# minutka_hlavni_v2.net
KiCad netlist of a schematic drawn in EAGLE
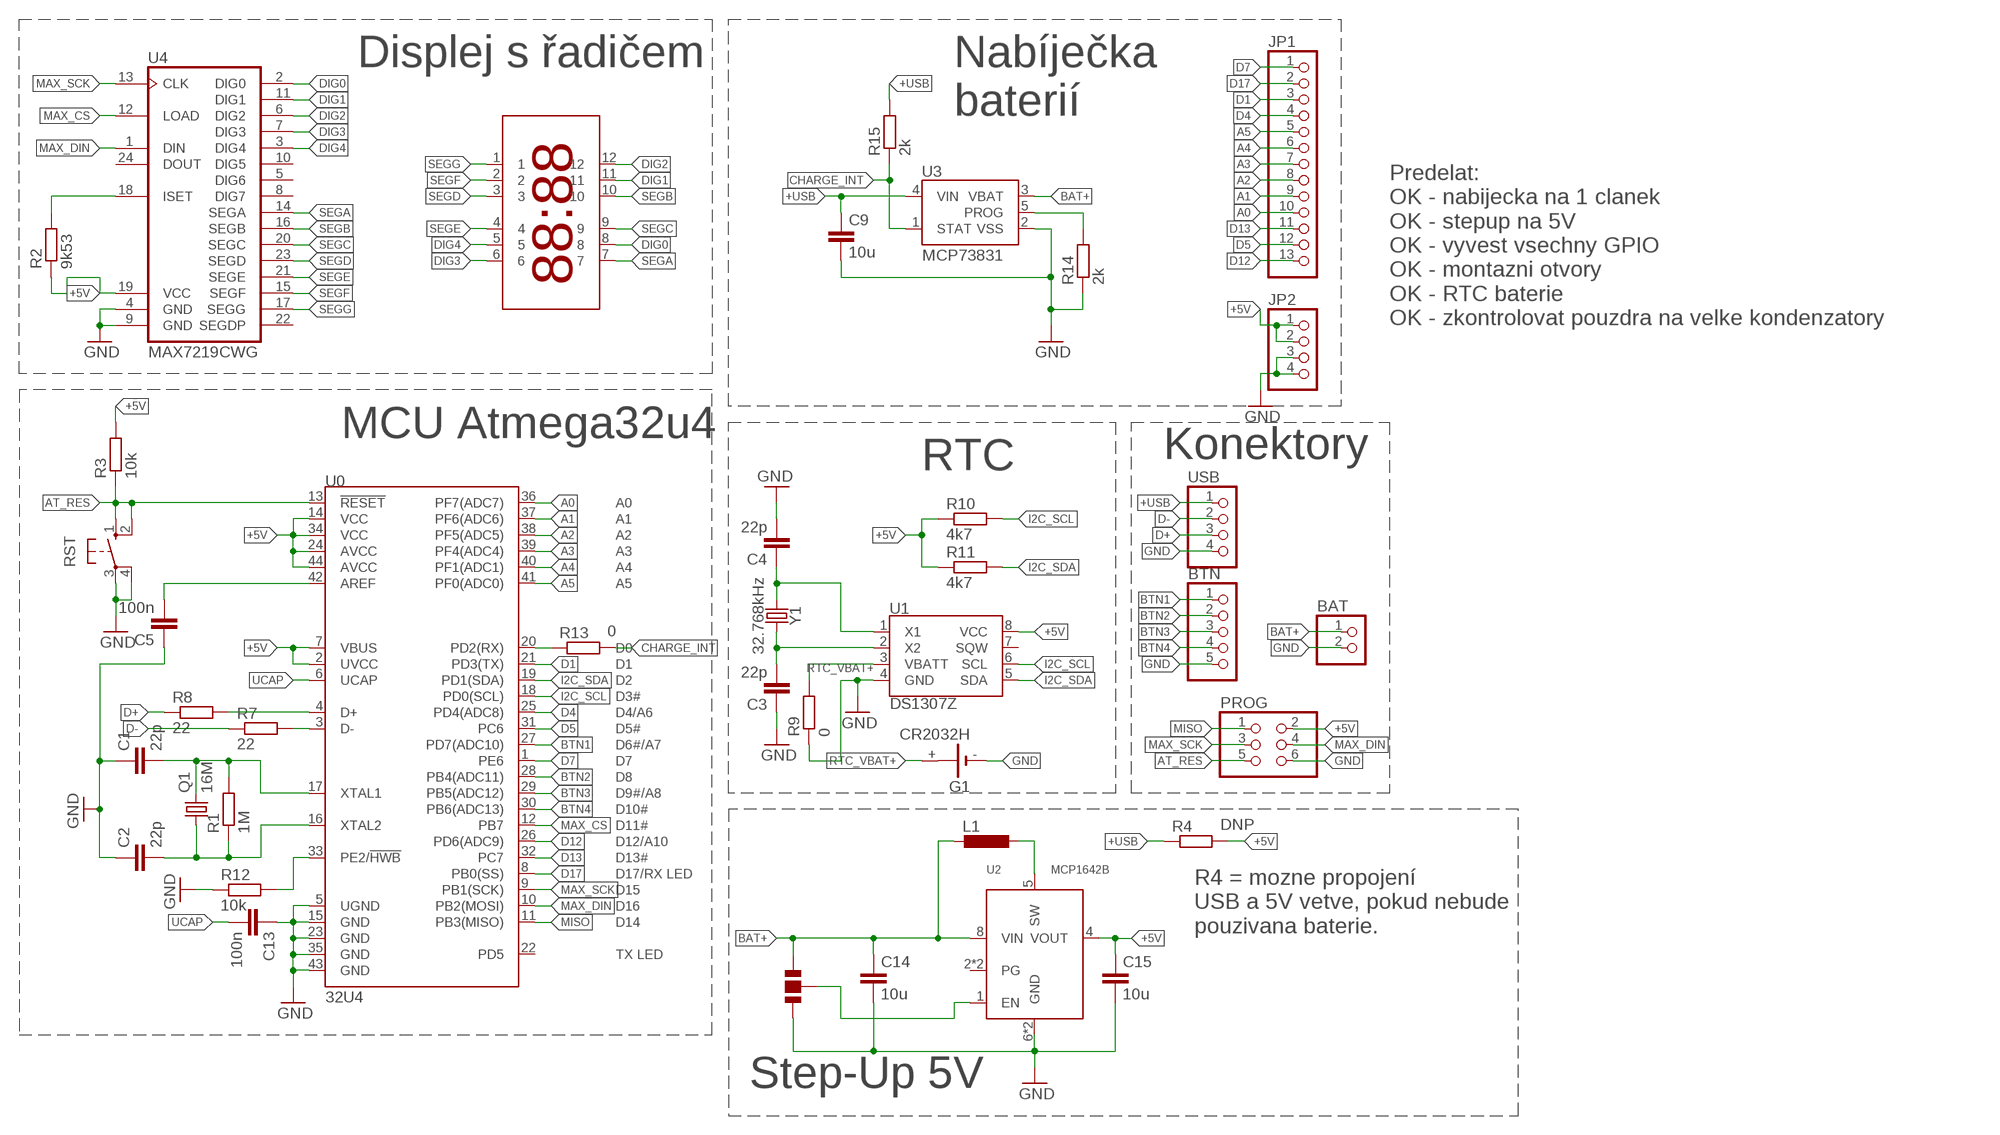
[diagram p0: schematic, sheet 1]

(export (version "E")
  (design (tool "Eeschema 10.0.6"))
  (components
    (comp (ref "BAT")
      (value "PINHD-1X2")
      (footprint "eagle-import:1X02")
      (libsource (lib "eagle-import") (part "PINHD-1X2"))
    )
    (comp (ref "BTN")
      (value "PINHD-1X5")
      (footprint "eagle-import:1X05")
      (libsource (lib "eagle-import") (part "PINHD-1X5"))
    )
    (comp (ref "C1")
      (value "22p")
      (footprint "eagle-import:C0603")
      (libsource (lib "eagle-import") (part "C-EUC0603"))
    )
    (comp (ref "C2")
      (value "22p")
      (footprint "eagle-import:C0603")
      (libsource (lib "eagle-import") (part "C-EUC0603"))
    )
    (comp (ref "C3")
      (value "22p")
      (footprint "eagle-import:C0603")
      (libsource (lib "eagle-import") (part "C-EUC0603"))
    )
    (comp (ref "C4")
      (value "22p")
      (footprint "eagle-import:C0603")
      (libsource (lib "eagle-import") (part "C-EUC0603"))
    )
    (comp (ref "C5")
      (value "100n")
      (footprint "eagle-import:C0603")
      (libsource (lib "eagle-import") (part "C-EUC0603"))
    )
    (comp (ref "C9")
      (value "10u")
      (footprint "eagle-import:C1206")
      (libsource (lib "eagle-import") (part "C-EUC1206"))
    )
    (comp (ref "C13")
      (value "100n")
      (footprint "eagle-import:C0603")
      (libsource (lib "eagle-import") (part "C-EUC0603"))
    )
    (comp (ref "C14")
      (value "10u")
      (footprint "eagle-import:C1206")
      (libsource (lib "eagle-import") (part "C-EUC1206"))
    )
    (comp (ref "C15")
      (value "10u")
      (footprint "eagle-import:C1206")
      (libsource (lib "eagle-import") (part "C-EUC1206"))
    )
    (comp (ref "G1")
      (value "CR2032H")
      (footprint "eagle-import:CR2032H")
      (libsource (lib "eagle-import") (part "CR2032H"))
    )
    (comp (ref "JP1")
      (value "PINHD-1X13")
      (footprint "eagle-import:1X13")
      (libsource (lib "eagle-import") (part "PINHD-1X13"))
    )
    (comp (ref "JP2")
      (value "PINHD-1X4")
      (footprint "eagle-import:1X04")
      (libsource (lib "eagle-import") (part "PINHD-1X4"))
    )
    (comp (ref "L1")
      (value "L-EUL4532P")
      (footprint "eagle-import:L4532P")
      (libsource (lib "eagle-import") (part "L-EUL4532P"))
    )
    (comp (ref "PROG")
      (value "PINHD-2X3")
      (footprint "eagle-import:2X03")
      (libsource (lib "eagle-import") (part "PINHD-2X3"))
    )
    (comp (ref "Q1")
      (value "16M")
      (footprint "eagle-import:HC49UP")
      (libsource (lib "eagle-import") (part "CRYSTALHC49UP"))
    )
    (comp (ref "R1")
      (value "1M")
      (footprint "eagle-import:R0603")
      (libsource (lib "eagle-import") (part "R-EU_R0603"))
    )
    (comp (ref "R2")
      (value "9k53")
      (footprint "eagle-import:R0603")
      (libsource (lib "eagle-import") (part "R-EU_R0603"))
    )
    (comp (ref "R3")
      (value "10k")
      (footprint "eagle-import:R0603")
      (libsource (lib "eagle-import") (part "R-EU_R0603"))
    )
    (comp (ref "R4")
      (value "DNP")
      (footprint "eagle-import:R0603")
      (libsource (lib "eagle-import") (part "R-EU_R0603"))
    )
    (comp (ref "R7")
      (value "22")
      (footprint "eagle-import:R0603")
      (libsource (lib "eagle-import") (part "R-EU_R0603"))
    )
    (comp (ref "R8")
      (value "22")
      (footprint "eagle-import:R0603")
      (libsource (lib "eagle-import") (part "R-EU_R0603"))
    )
    (comp (ref "R9")
      (value "0")
      (footprint "eagle-import:R0603")
      (libsource (lib "eagle-import") (part "R-EU_R0603"))
    )
    (comp (ref "R10")
      (value "4k7")
      (footprint "eagle-import:R0603")
      (libsource (lib "eagle-import") (part "R-EU_R0603"))
    )
    (comp (ref "R11")
      (value "4k7")
      (footprint "eagle-import:R0603")
      (libsource (lib "eagle-import") (part "R-EU_R0603"))
    )
    (comp (ref "R12")
      (value "10k")
      (footprint "eagle-import:R0603")
      (libsource (lib "eagle-import") (part "R-EU_R0603"))
    )
    (comp (ref "R13")
      (value "0")
      (footprint "eagle-import:R0603")
      (libsource (lib "eagle-import") (part "R-EU_R0603"))
    )
    (comp (ref "R14")
      (value "2k")
      (footprint "eagle-import:R0603")
      (libsource (lib "eagle-import") (part "R-EU_R0603"))
    )
    (comp (ref "R15")
      (value "2k")
      (footprint "eagle-import:R0603")
      (libsource (lib "eagle-import") (part "R-EU_R0603"))
    )
    (comp (ref "RST")
      (value "10-XX")
      (footprint "eagle-import:B3F-10XX")
      (fields (field (name "MPN") "B3F-1000"))
      (libsource (lib "eagle-import") (part "10-XX"))
    )
    (comp (ref "U$2")
      (value "KW4-8828AVB")
      (footprint "eagle-import:KW4-8828AVB")
      (libsource (lib "eagle-import") (part "KW4-8828AVB"))
    )
    (comp (ref "U$7")
      (value "JUMPER")
      (footprint "eagle-import:2-WAY")
      (libsource (lib "eagle-import") (part "JUMPER"))
    )
    (comp (ref "U0")
      (value "32U4")
      (footprint "eagle-import:TQFP44")
      (libsource (lib "eagle-import") (part "ATMEGA32U4TQFP-44"))
    )
    (comp (ref "U1")
      (value "DS1307Z")
      (footprint "eagle-import:SO08-0.15")
      (libsource (lib "eagle-import") (part "DS1307Z"))
    )
    (comp (ref "U2")
      (value "MCP1642B")
      (footprint "eagle-import:MSOP8")
      (libsource (lib "eagle-import") (part "MCP1642B"))
    )
    (comp (ref "U3")
      (value "MCP73831")
      (footprint "eagle-import:SOT95P290X120-5")
      (libsource (lib "eagle-import") (part "MCP73831"))
    )
    (comp (ref "U4")
      (value "MAX7219CWG")
      (footprint "eagle-import:SO24L")
      (libsource (lib "eagle-import") (part "MAX7219CWG"))
    )
    (comp (ref "USB")
      (value "PINHD-1X4")
      (footprint "eagle-import:1X04")
      (libsource (lib "eagle-import") (part "PINHD-1X4"))
    )
    (comp (ref "Y1")
      (value "32.768kHz")
      (footprint "eagle-import:CRYSTAL-SMD-2X6-CYL")
      (libsource (lib "eagle-import") (part "CRYSTAL-32.768KHZSMD-2X6"))
    )
  )
  (nets
    (net (code "1") (name "+5V") (class "Default")
      (node (ref "C15") (pin "1") (pinfunction "1_1") (pintype "passive"))
      (node (ref "JP2") (pin "1") (pinfunction "1_1") (pintype "passive"))
      (node (ref "JP2") (pin "2") (pinfunction "2_2") (pintype "passive"))
      (node (ref "PROG") (pin "2") (pinfunction "2_2") (pintype "passive"))
      (node (ref "R10") (pin "1") (pinfunction "1_1") (pintype "passive"))
      (node (ref "R11") (pin "1") (pinfunction "1_1") (pintype "passive"))
      (node (ref "R2") (pin "1") (pinfunction "1_1") (pintype "passive"))
      (node (ref "R3") (pin "2") (pinfunction "2_2") (pintype "passive"))
      (node (ref "R4") (pin "2") (pinfunction "2_2") (pintype "passive"))
      (node (ref "U0") (pin "14") (pinfunction "VCC_14") (pintype "bidirectional"))
      (node (ref "U0") (pin "2") (pinfunction "UVCC_2") (pintype "bidirectional"))
      (node (ref "U0") (pin "24") (pinfunction "AVCC_24") (pintype "bidirectional"))
      (node (ref "U0") (pin "34") (pinfunction "VCC_34") (pintype "bidirectional"))
      (node (ref "U0") (pin "44") (pinfunction "AVCC_44") (pintype "bidirectional"))
      (node (ref "U0") (pin "7") (pinfunction "VBUS_7") (pintype "bidirectional"))
      (node (ref "U1") (pin "8") (pinfunction "VCC_8") (pintype "bidirectional"))
      (node (ref "U2") (pin "4") (pinfunction "VOUT_4") (pintype "power_in"))
      (node (ref "U4") (pin "19") (pinfunction "VCC_19") (pintype "power_in"))
    )
    (net (code "2") (name "+USB") (class "Default")
      (node (ref "C9") (pin "1") (pinfunction "1_1") (pintype "passive"))
      (node (ref "R15") (pin "2") (pinfunction "2_2") (pintype "passive"))
      (node (ref "R4") (pin "1") (pinfunction "1_1") (pintype "passive"))
      (node (ref "U3") (pin "4") (pinfunction "VIN_4") (pintype "power_in"))
      (node (ref "USB") (pin "1") (pinfunction "1_1") (pintype "passive"))
    )
    (net (code "3") (name "A0") (class "Default")
      (node (ref "JP1") (pin "10") (pinfunction "10_10") (pintype "passive"))
      (node (ref "U0") (pin "36") (pinfunction "PF7(ADC7)_36") (pintype "bidirectional"))
    )
    (net (code "4") (name "A1") (class "Default")
      (node (ref "JP1") (pin "9") (pinfunction "9_9") (pintype "passive"))
      (node (ref "U0") (pin "37") (pinfunction "PF6(ADC6)_37") (pintype "bidirectional"))
    )
    (net (code "5") (name "A2") (class "Default")
      (node (ref "JP1") (pin "8") (pinfunction "8_8") (pintype "passive"))
      (node (ref "U0") (pin "38") (pinfunction "PF5(ADC5)_38") (pintype "bidirectional"))
    )
    (net (code "6") (name "A3") (class "Default")
      (node (ref "JP1") (pin "7") (pinfunction "7_7") (pintype "passive"))
      (node (ref "U0") (pin "39") (pinfunction "PF4(ADC4)_39") (pintype "bidirectional"))
    )
    (net (code "7") (name "A4") (class "Default")
      (node (ref "JP1") (pin "6") (pinfunction "6_6") (pintype "passive"))
      (node (ref "U0") (pin "40") (pinfunction "PF1(ADC1)_40") (pintype "bidirectional"))
    )
    (net (code "8") (name "A5") (class "Default")
      (node (ref "JP1") (pin "5") (pinfunction "5_5") (pintype "passive"))
      (node (ref "U0") (pin "41") (pinfunction "PF0(ADC0)_41") (pintype "bidirectional"))
    )
    (net (code "9") (name "AT_RES") (class "Default")
      (node (ref "PROG") (pin "5") (pinfunction "5_5") (pintype "passive"))
      (node (ref "R3") (pin "1") (pinfunction "1_1") (pintype "passive"))
      (node (ref "RST") (pin "1") (pinfunction "S_1") (pintype "passive"))
      (node (ref "RST") (pin "2") (pinfunction "S1_2") (pintype "passive"))
      (node (ref "U0") (pin "13") (pinfunction "~{RESET}_13") (pintype "bidirectional"))
    )
    (net (code "10") (name "BAT+") (class "Default")
      (node (ref "BAT") (pin "1") (pinfunction "1_1") (pintype "passive"))
      (node (ref "C14") (pin "1") (pinfunction "1_1") (pintype "passive"))
      (node (ref "L1") (pin "2") (pinfunction "2_2") (pintype "passive"))
      (node (ref "U$7") (pin "P$2") (pinfunction "P$2_P$2") (pintype "bidirectional"))
      (node (ref "U2") (pin "8") (pinfunction "VIN_8") (pintype "power_in"))
      (node (ref "U3") (pin "3") (pinfunction "VBAT_3") (pintype "power_in"))
    )
    (net (code "11") (name "BTN1") (class "Default")
      (node (ref "BTN") (pin "1") (pinfunction "1_1") (pintype "passive"))
      (node (ref "U0") (pin "27") (pinfunction "PD7(ADC10)_27") (pintype "bidirectional"))
    )
    (net (code "12") (name "BTN2") (class "Default")
      (node (ref "BTN") (pin "2") (pinfunction "2_2") (pintype "passive"))
      (node (ref "U0") (pin "28") (pinfunction "PB4(ADC11)_28") (pintype "bidirectional"))
    )
    (net (code "13") (name "BTN3") (class "Default")
      (node (ref "BTN") (pin "3") (pinfunction "3_3") (pintype "passive"))
      (node (ref "U0") (pin "29") (pinfunction "PB5(ADC12)_29") (pintype "bidirectional"))
    )
    (net (code "14") (name "BTN4") (class "Default")
      (node (ref "BTN") (pin "4") (pinfunction "4_4") (pintype "passive"))
      (node (ref "U0") (pin "30") (pinfunction "PB6(ADC13)_30") (pintype "bidirectional"))
    )
    (net (code "15") (name "CHARGE_INT") (class "Default")
      (node (ref "R13") (pin "2") (pinfunction "2_2") (pintype "passive"))
      (node (ref "R15") (pin "1") (pinfunction "1_1") (pintype "passive"))
      (node (ref "U3") (pin "1") (pinfunction "STAT_1") (pintype "output"))
    )
    (net (code "16") (name "D+") (class "Default")
      (node (ref "R8") (pin "1") (pinfunction "1_1") (pintype "passive"))
      (node (ref "USB") (pin "3") (pinfunction "3_3") (pintype "passive"))
    )
    (net (code "17") (name "D-") (class "Default")
      (node (ref "R7") (pin "1") (pinfunction "1_1") (pintype "passive"))
      (node (ref "USB") (pin "2") (pinfunction "2_2") (pintype "passive"))
    )
    (net (code "18") (name "D1") (class "Default")
      (node (ref "JP1") (pin "3") (pinfunction "3_3") (pintype "passive"))
      (node (ref "U0") (pin "21") (pinfunction "PD3(TX)_21") (pintype "bidirectional"))
    )
    (net (code "19") (name "D4") (class "Default")
      (node (ref "JP1") (pin "4") (pinfunction "4_4") (pintype "passive"))
      (node (ref "U0") (pin "25") (pinfunction "PD4(ADC8)_25") (pintype "bidirectional"))
    )
    (net (code "20") (name "D5") (class "Default")
      (node (ref "JP1") (pin "12") (pinfunction "12_12") (pintype "passive"))
      (node (ref "U0") (pin "31") (pinfunction "PC6_31") (pintype "bidirectional"))
    )
    (net (code "21") (name "D7") (class "Default")
      (node (ref "JP1") (pin "1") (pinfunction "1_1") (pintype "passive"))
      (node (ref "U0") (pin "1") (pinfunction "PE6_1") (pintype "bidirectional"))
    )
    (net (code "22") (name "D12") (class "Default")
      (node (ref "JP1") (pin "13") (pinfunction "13_13") (pintype "passive"))
      (node (ref "U0") (pin "26") (pinfunction "PD6(ADC9)_26") (pintype "bidirectional"))
    )
    (net (code "23") (name "D13") (class "Default")
      (node (ref "JP1") (pin "11") (pinfunction "11_11") (pintype "passive"))
      (node (ref "U0") (pin "32") (pinfunction "PC7_32") (pintype "bidirectional"))
    )
    (net (code "24") (name "D17") (class "Default")
      (node (ref "JP1") (pin "2") (pinfunction "2_2") (pintype "passive"))
      (node (ref "U0") (pin "8") (pinfunction "PB0(SS)_8") (pintype "bidirectional"))
    )
    (net (code "25") (name "DIG0") (class "Default")
      (node (ref "U$2") (pin "8") (pinfunction "8_8") (pintype "bidirectional"))
      (node (ref "U4") (pin "2") (pinfunction "DIG0_2") (pintype "output"))
    )
    (net (code "26") (name "DIG1") (class "Default")
      (node (ref "U$2") (pin "11") (pinfunction "11_11") (pintype "bidirectional"))
      (node (ref "U4") (pin "11") (pinfunction "DIG1_11") (pintype "output"))
    )
    (net (code "27") (name "DIG2") (class "Default")
      (node (ref "U$2") (pin "12") (pinfunction "12_12") (pintype "bidirectional"))
      (node (ref "U4") (pin "6") (pinfunction "DIG2_6") (pintype "output"))
    )
    (net (code "28") (name "DIG3") (class "Default")
      (node (ref "U$2") (pin "6") (pinfunction "6_6") (pintype "bidirectional"))
      (node (ref "U4") (pin "7") (pinfunction "DIG3_7") (pintype "output"))
    )
    (net (code "29") (name "DIG4") (class "Default")
      (node (ref "U$2") (pin "5") (pinfunction "5_5") (pintype "bidirectional"))
      (node (ref "U4") (pin "3") (pinfunction "DIG4_3") (pintype "output"))
    )
    (net (code "30") (name "GND") (class "Default")
      (node (ref "BAT") (pin "2") (pinfunction "2_2") (pintype "passive"))
      (node (ref "BTN") (pin "5") (pinfunction "5_5") (pintype "passive"))
      (node (ref "C1") (pin "1") (pinfunction "1_1") (pintype "passive"))
      (node (ref "C13") (pin "1") (pinfunction "1_1") (pintype "passive"))
      (node (ref "C14") (pin "2") (pinfunction "2_2") (pintype "passive"))
      (node (ref "C15") (pin "2") (pinfunction "2_2") (pintype "passive"))
      (node (ref "C2") (pin "1") (pinfunction "1_1") (pintype "passive"))
      (node (ref "C3") (pin "1") (pinfunction "1_1") (pintype "passive"))
      (node (ref "C4") (pin "2") (pinfunction "2_2") (pintype "passive"))
      (node (ref "C5") (pin "1") (pinfunction "1_1") (pintype "passive"))
      (node (ref "C9") (pin "2") (pinfunction "2_2") (pintype "passive"))
      (node (ref "G1") (pin "-") (pinfunction "-_-") (pintype "passive"))
      (node (ref "JP2") (pin "3") (pinfunction "3_3") (pintype "passive"))
      (node (ref "JP2") (pin "4") (pinfunction "4_4") (pintype "passive"))
      (node (ref "PROG") (pin "6") (pinfunction "6_6") (pintype "passive"))
      (node (ref "R12") (pin "1") (pinfunction "1_1") (pintype "passive"))
      (node (ref "R14") (pin "1") (pinfunction "1_1") (pintype "passive"))
      (node (ref "R9") (pin "1") (pinfunction "1_1") (pintype "passive"))
      (node (ref "RST") (pin "3") (pinfunction "P_3") (pintype "passive"))
      (node (ref "RST") (pin "4") (pinfunction "P1_4") (pintype "passive"))
      (node (ref "U$7") (pin "P$3") (pinfunction "P$3_P$3") (pintype "bidirectional"))
      (node (ref "U0") (pin "15") (pinfunction "GND_15") (pintype "bidirectional"))
      (node (ref "U0") (pin "23") (pinfunction "GND_23") (pintype "bidirectional"))
      (node (ref "U0") (pin "35") (pinfunction "GND_35") (pintype "bidirectional"))
      (node (ref "U0") (pin "43") (pinfunction "GND_43") (pintype "bidirectional"))
      (node (ref "U0") (pin "5") (pinfunction "UGND_5") (pintype "bidirectional"))
      (node (ref "U1") (pin "4") (pinfunction "GND_4") (pintype "bidirectional"))
      (node (ref "U2") (pin "6") (pinfunction "GND_6") (pintype "power_in"))
      (node (ref "U2") (pin "7") (pinfunction "GND_7") (pintype "power_in"))
      (node (ref "U3") (pin "2") (pinfunction "VSS_2") (pintype "power_in"))
      (node (ref "U4") (pin "4") (pinfunction "GND_4") (pintype "power_in"))
      (node (ref "U4") (pin "9") (pinfunction "GND_9") (pintype "power_in"))
      (node (ref "USB") (pin "4") (pinfunction "4_4") (pintype "passive"))
    )
    (net (code "31") (name "I2C_SCL") (class "Default")
      (node (ref "R10") (pin "2") (pinfunction "2_2") (pintype "passive"))
      (node (ref "U0") (pin "18") (pinfunction "PD0(SCL)_18") (pintype "bidirectional"))
      (node (ref "U1") (pin "6") (pinfunction "SCL_6") (pintype "bidirectional"))
    )
    (net (code "32") (name "I2C_SDA") (class "Default")
      (node (ref "R11") (pin "2") (pinfunction "2_2") (pintype "passive"))
      (node (ref "U0") (pin "19") (pinfunction "PD1(SDA)_19") (pintype "bidirectional"))
      (node (ref "U1") (pin "5") (pinfunction "SDA_5") (pintype "bidirectional"))
    )
    (net (code "33") (name "MAX_CS") (class "Default")
      (node (ref "U0") (pin "12") (pinfunction "PB7_12") (pintype "bidirectional"))
      (node (ref "U4") (pin "12") (pinfunction "LOAD_12") (pintype "input"))
    )
    (net (code "34") (name "MAX_DIN") (class "Default")
      (node (ref "PROG") (pin "4") (pinfunction "4_4") (pintype "passive"))
      (node (ref "U0") (pin "10") (pinfunction "PB2(MOSI)_10") (pintype "bidirectional"))
      (node (ref "U4") (pin "1") (pinfunction "DIN_1") (pintype "input"))
    )
    (net (code "35") (name "MAX_SCK") (class "Default")
      (node (ref "PROG") (pin "3") (pinfunction "3_3") (pintype "passive"))
      (node (ref "U0") (pin "9") (pinfunction "PB1(SCK)_9") (pintype "bidirectional"))
      (node (ref "U4") (pin "13") (pinfunction "CLK_13") (pintype "input"))
    )
    (net (code "36") (name "MISO") (class "Default")
      (node (ref "PROG") (pin "1") (pinfunction "1_1") (pintype "passive"))
      (node (ref "U0") (pin "11") (pinfunction "PB3(MISO)_11") (pintype "bidirectional"))
    )
    (net (code "37") (name "Net-(U0-AREF)") (class "Default")
      (node (ref "C5") (pin "2") (pinfunction "2_2") (pintype "passive"))
      (node (ref "U0") (pin "42") (pinfunction "AREF_42") (pintype "bidirectional"))
    )
    (net (code "38") (name "Net-(U0-D+)") (class "Default")
      (node (ref "R8") (pin "2") (pinfunction "2_2") (pintype "passive"))
      (node (ref "U0") (pin "4") (pinfunction "D+_4") (pintype "bidirectional"))
    )
    (net (code "39") (name "Net-(U0-D-)") (class "Default")
      (node (ref "R7") (pin "2") (pinfunction "2_2") (pintype "passive"))
      (node (ref "U0") (pin "3") (pinfunction "D-_3") (pintype "bidirectional"))
    )
    (net (code "40") (name "Net-(U0-PD2(RX))") (class "Default")
      (node (ref "R13") (pin "1") (pinfunction "1_1") (pintype "passive"))
      (node (ref "U0") (pin "20") (pinfunction "PD2(RX)_20") (pintype "bidirectional"))
    )
    (net (code "41") (name "Net-(U0-PE2{slash}~{HWB})") (class "Default")
      (node (ref "R12") (pin "2") (pinfunction "2_2") (pintype "passive"))
      (node (ref "U0") (pin "33") (pinfunction "PE2/~{HWB}_33") (pintype "bidirectional"))
    )
    (net (code "42") (name "Net-(U0-XTAL1)") (class "Default")
      (node (ref "C1") (pin "2") (pinfunction "2_2") (pintype "passive"))
      (node (ref "Q1") (pin "2") (pinfunction "2_2") (pintype "passive"))
      (node (ref "R1") (pin "2") (pinfunction "2_2") (pintype "passive"))
      (node (ref "U0") (pin "17") (pinfunction "XTAL1_17") (pintype "bidirectional"))
    )
    (net (code "43") (name "Net-(U0-XTAL2)") (class "Default")
      (node (ref "C2") (pin "2") (pinfunction "2_2") (pintype "passive"))
      (node (ref "Q1") (pin "1") (pinfunction "1_1") (pintype "passive"))
      (node (ref "R1") (pin "1") (pinfunction "1_1") (pintype "passive"))
      (node (ref "U0") (pin "16") (pinfunction "XTAL2_16") (pintype "bidirectional"))
    )
    (net (code "44") (name "Net-(U1-X1)") (class "Default")
      (node (ref "C4") (pin "1") (pinfunction "1_1") (pintype "passive"))
      (node (ref "U1") (pin "1") (pinfunction "X1_1") (pintype "bidirectional"))
      (node (ref "Y1") (pin "X1") (pinfunction "1_X1") (pintype "passive"))
    )
    (net (code "45") (name "Net-(U1-X2)") (class "Default")
      (node (ref "C3") (pin "2") (pinfunction "2_2") (pintype "passive"))
      (node (ref "U1") (pin "2") (pinfunction "X2_2") (pintype "bidirectional"))
      (node (ref "Y1") (pin "X2") (pinfunction "2_X2") (pintype "passive"))
    )
    (net (code "46") (name "Net-(U2-EN)") (class "Default")
      (node (ref "U$7") (pin "P$1") (pinfunction "P$1_P$1") (pintype "bidirectional"))
      (node (ref "U2") (pin "1") (pinfunction "EN_1") (pintype "input"))
    )
    (net (code "47") (name "Net-(U2-SW)") (class "Default")
      (node (ref "L1") (pin "1") (pinfunction "1_1") (pintype "passive"))
      (node (ref "U2") (pin "5") (pinfunction "SW_5") (pintype "power_in"))
    )
    (net (code "48") (name "Net-(U3-PROG)") (class "Default")
      (node (ref "R14") (pin "2") (pinfunction "2_2") (pintype "passive"))
      (node (ref "U3") (pin "5") (pinfunction "PROG_5") (pintype "input"))
    )
    (net (code "49") (name "Net-(U4-ISET)") (class "Default")
      (node (ref "R2") (pin "2") (pinfunction "2_2") (pintype "passive"))
      (node (ref "U4") (pin "18") (pinfunction "ISET_18") (pintype "input"))
    )
    (net (code "50") (name "RTC_VBAT+") (class "Default")
      (node (ref "G1") (pin "+") (pinfunction "+_+") (pintype "passive"))
      (node (ref "R9") (pin "2") (pinfunction "2_2") (pintype "passive"))
      (node (ref "U1") (pin "3") (pinfunction "VBATT_3") (pintype "bidirectional"))
    )
    (net (code "51") (name "SEGA") (class "Default")
      (node (ref "U$2") (pin "7") (pinfunction "7_7") (pintype "bidirectional"))
      (node (ref "U4") (pin "14") (pinfunction "SEGA_14") (pintype "output"))
    )
    (net (code "52") (name "SEGB") (class "Default")
      (node (ref "U$2") (pin "10") (pinfunction "10_10") (pintype "bidirectional"))
      (node (ref "U4") (pin "16") (pinfunction "SEGB_16") (pintype "output"))
    )
    (net (code "53") (name "SEGC") (class "Default")
      (node (ref "U$2") (pin "9") (pinfunction "9_9") (pintype "bidirectional"))
      (node (ref "U4") (pin "20") (pinfunction "SEGC_20") (pintype "output"))
    )
    (net (code "54") (name "SEGD") (class "Default")
      (node (ref "U$2") (pin "3") (pinfunction "3_3") (pintype "bidirectional"))
      (node (ref "U4") (pin "23") (pinfunction "SEGD_23") (pintype "output"))
    )
    (net (code "55") (name "SEGE") (class "Default")
      (node (ref "U$2") (pin "4") (pinfunction "4_4") (pintype "bidirectional"))
      (node (ref "U4") (pin "21") (pinfunction "SEGE_21") (pintype "output"))
    )
    (net (code "56") (name "SEGF") (class "Default")
      (node (ref "U$2") (pin "2") (pinfunction "2_2") (pintype "bidirectional"))
      (node (ref "U4") (pin "15") (pinfunction "SEGF_15") (pintype "output"))
    )
    (net (code "57") (name "SEGG") (class "Default")
      (node (ref "U$2") (pin "1") (pinfunction "1_1") (pintype "bidirectional"))
      (node (ref "U4") (pin "17") (pinfunction "SEGG_17") (pintype "output"))
    )
    (net (code "58") (name "UCAP") (class "Default")
      (node (ref "C13") (pin "2") (pinfunction "2_2") (pintype "passive"))
      (node (ref "U0") (pin "6") (pinfunction "UCAP_6") (pintype "bidirectional"))
    )
    (net (code "59") (name "unconnected-(G1-+-Pad+@1)") (class "Default")
      (node (ref "G1") (pin "+@1") (pinfunction "+_+@1") (pintype "passive"))
    )
    (net (code "60") (name "unconnected-(U0-PD5-Pad22)") (class "Default")
      (node (ref "U0") (pin "22") (pinfunction "PD5_22") (pintype "bidirectional"))
    )
    (net (code "61") (name "unconnected-(U1-SQW-Pad7)") (class "Default")
      (node (ref "U1") (pin "7") (pinfunction "SQW_7") (pintype "bidirectional"))
    )
    (net (code "62") (name "unconnected-(U2-PG-Pad2)") (class "Default")
      (node (ref "U2") (pin "2") (pinfunction "PG_2") (pintype "no_connect"))
    )
    (net (code "63") (name "unconnected-(U2-PG-Pad3)") (class "Default")
      (node (ref "U2") (pin "3") (pinfunction "PG_3") (pintype "no_connect"))
    )
    (net (code "64") (name "unconnected-(U4-DIG5-Pad10)") (class "Default")
      (node (ref "U4") (pin "10") (pinfunction "DIG5_10") (pintype "output"))
    )
    (net (code "65") (name "unconnected-(U4-DIG6-Pad5)") (class "Default")
      (node (ref "U4") (pin "5") (pinfunction "DIG6_5") (pintype "output"))
    )
    (net (code "66") (name "unconnected-(U4-DIG7-Pad8)") (class "Default")
      (node (ref "U4") (pin "8") (pinfunction "DIG7_8") (pintype "output"))
    )
    (net (code "67") (name "unconnected-(U4-DOUT-Pad24)") (class "Default")
      (node (ref "U4") (pin "24") (pinfunction "DOUT_24") (pintype "output"))
    )
    (net (code "68") (name "unconnected-(U4-SEGDP-Pad22)") (class "Default")
      (node (ref "U4") (pin "22") (pinfunction "SEGDP_22") (pintype "output"))
    )
  )
)
